# user_interface.net
KiCad netlist of a schematic drawn in Altium Designer
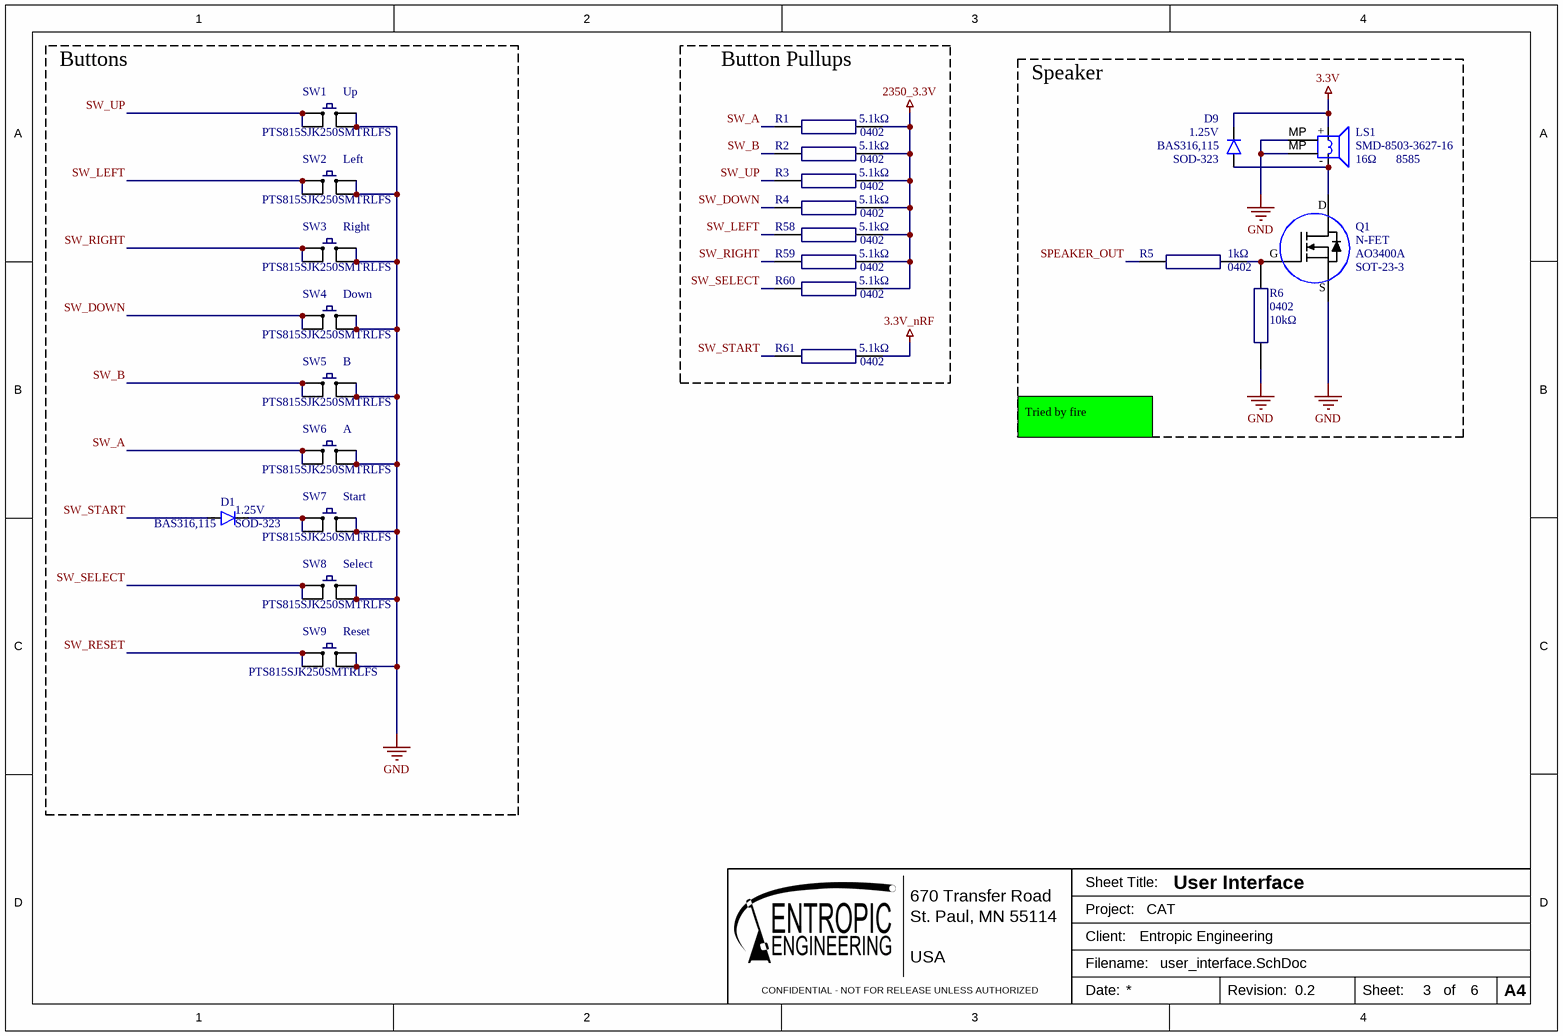
[diagram p0: user_interface.SchDoc]

(export (version "E")
  (design (tool "Eeschema 10.0.6"))
  (components
    (comp (ref "D1")
      (value "BAS316,115")
      (footprint "SOD-323")
      (description "1.25 V, 100 V max, 150 mA, 4 ns diode, SOD-323")
      (fields
        (field (name "MANUFACTURER") "Nexperia")
        (field (name "MANUFACTURER PART NUMBER") "BAS316,115")
        (field (name "FORWARD VOLTAGE") "1.25V")
        (field (name "PACKAGE") "SOD-323")
      )
      (libsource (lib "cat") (part "BAS316,115"))
    )
    (comp (ref "D9")
      (value "BAS316,115")
      (footprint "SOD-323")
      (description "1.25 V, 100 V max, 150 mA, 4 ns diode, SOD-323")
      (fields
        (field (name "MANUFACTURER") "Nexperia")
        (field (name "MANUFACTURER PART NUMBER") "BAS316,115")
        (field (name "FORWARD VOLTAGE") "1.25V")
        (field (name "PACKAGE") "SOD-323")
      )
      (libsource (lib "cat") (part "BAS316,115"))
    )
    (comp (ref "LS1")
      (value "SMD-8503-3627-16")
      (footprint "8585_speaker")
      (description "16 Ω, 8.5 mm x 8.5 mm, SMD speaker")
      (fields
        (field (name "MANUFACTURER") "S&S")
        (field (name "RESISTANCE") "16Ω")
        (field (name "PACKAGE") "8585")
        (field (name "MANUFACTURER PART NUMBER") "SMD-8503-3627-16")
      )
      (libsource (lib "cat") (part "SMD-8503-3627-16"))
    )
    (comp (ref "Q1")
      (value "N-FET")
      (footprint "SOT95P280X115-3N")
      (description "N-FET, 30V, 5.7A, SOT-23-3")
      (fields
        (field (name "MANUFACTURER") "Alpha & Omega Semiconductor")
        (field (name "CASE/PACKAGE") "SOT-23-3")
        (field (name "MANUFACTURER PART NUMBER") "AO3400A")
        (field (name "HOUSE_PART_NUMBER") "AO3400A")
      )
      (libsource (lib "cat") (part "AO3400A"))
    )
    (comp (ref "R1")
      (value "5.1kΩ")
      (footprint "0402_resistor")
      (description "5.1 kΩ, 0402 Chip resistor")
      (fields
        (field (name "MANUFACTURER") "Yageo")
        (field (name "MANUFACTURER PART NUMBER") "RC0402FR-075K1L")
        (field (name "CASE/PACKAGE") "0402")
      )
      (libsource (lib "cat") (part "RC0402FR-075K1L"))
    )
    (comp (ref "R2")
      (value "5.1kΩ")
      (footprint "0402_resistor")
      (description "5.1 kΩ, 0402 Chip resistor")
      (fields
        (field (name "MANUFACTURER") "Yageo")
        (field (name "MANUFACTURER PART NUMBER") "RC0402FR-075K1L")
        (field (name "CASE/PACKAGE") "0402")
      )
      (libsource (lib "cat") (part "RC0402FR-075K1L"))
    )
    (comp (ref "R3")
      (value "5.1kΩ")
      (footprint "0402_resistor")
      (description "5.1 kΩ, 0402 Chip resistor")
      (fields
        (field (name "MANUFACTURER") "Yageo")
        (field (name "MANUFACTURER PART NUMBER") "RC0402FR-075K1L")
        (field (name "CASE/PACKAGE") "0402")
      )
      (libsource (lib "cat") (part "RC0402FR-075K1L"))
    )
    (comp (ref "R4")
      (value "5.1kΩ")
      (footprint "0402_resistor")
      (description "5.1 kΩ, 0402 Chip resistor")
      (fields
        (field (name "MANUFACTURER") "Yageo")
        (field (name "MANUFACTURER PART NUMBER") "RC0402FR-075K1L")
        (field (name "CASE/PACKAGE") "0402")
      )
      (libsource (lib "cat") (part "RC0402FR-075K1L"))
    )
    (comp (ref "R5")
      (value "1kΩ")
      (footprint "0402_resistor")
      (description "1 kΩ, 0402 Chip resistor")
      (fields
        (field (name "MANUFACTURER") "Yageo")
        (field (name "MANUFACTURER PART NUMBER") "RC0402JR-071KL")
        (field (name "CASE/PACKAGE") "0402")
      )
      (libsource (lib "cat") (part "RC0402JR-071KL"))
    )
    (comp (ref "R6")
      (value "10kΩ")
      (footprint "0402_resistor")
      (description "10 kΩ, 0402 Chip resistor")
      (fields
        (field (name "MANUFACTURER") "Yageo")
        (field (name "MANUFACTURER PART NUMBER") "RC0402FR-0710KL")
        (field (name "CASE CODE (IMPERIAL)") "0402")
      )
      (libsource (lib "cat") (part "RC0402FR-0710KL"))
    )
    (comp (ref "R58")
      (value "5.1kΩ")
      (footprint "0402_resistor")
      (description "5.1 kΩ, 0402 Chip resistor")
      (fields
        (field (name "MANUFACTURER") "Yageo")
        (field (name "MANUFACTURER PART NUMBER") "RC0402FR-075K1L")
        (field (name "CASE/PACKAGE") "0402")
      )
      (libsource (lib "cat") (part "RC0402FR-075K1L"))
    )
    (comp (ref "R59")
      (value "5.1kΩ")
      (footprint "0402_resistor")
      (description "5.1 kΩ, 0402 Chip resistor")
      (fields
        (field (name "MANUFACTURER") "Yageo")
        (field (name "MANUFACTURER PART NUMBER") "RC0402FR-075K1L")
        (field (name "CASE/PACKAGE") "0402")
      )
      (libsource (lib "cat") (part "RC0402FR-075K1L"))
    )
    (comp (ref "R60")
      (value "5.1kΩ")
      (footprint "0402_resistor")
      (description "5.1 kΩ, 0402 Chip resistor")
      (fields
        (field (name "MANUFACTURER") "Yageo")
        (field (name "MANUFACTURER PART NUMBER") "RC0402FR-075K1L")
        (field (name "CASE/PACKAGE") "0402")
      )
      (libsource (lib "cat") (part "RC0402FR-075K1L"))
    )
    (comp (ref "R61")
      (value "5.1kΩ")
      (footprint "0402_resistor")
      (description "5.1 kΩ, 0402 Chip resistor")
      (fields
        (field (name "MANUFACTURER") "Yageo")
        (field (name "MANUFACTURER PART NUMBER") "RC0402FR-075K1L")
        (field (name "CASE/PACKAGE") "0402")
      )
      (libsource (lib "cat") (part "RC0402FR-075K1L"))
    )
    (comp (ref "SW1")
      (value "Up")
      (footprint "PTS815")
      (description "Surface Mount Tactile Switch, Momentary SPST-NO 50mA 12VDC, 250gf, 4.2x3.2mm")
      (fields
        (field (name "MANUFACTURER PART NUMBER") "PTS815SJK250SMTRLFS")
        (field (name "MANUFACTURER") "ITT C&K")
      )
      (libsource (lib "cat") (part "PTS815SJK250SMTRLFS"))
    )
    (comp (ref "SW2")
      (value "Left")
      (footprint "PTS815")
      (description "Surface Mount Tactile Switch, Momentary SPST-NO 50mA 12VDC, 250gf, 4.2x3.2mm")
      (fields
        (field (name "MANUFACTURER PART NUMBER") "PTS815SJK250SMTRLFS")
        (field (name "MANUFACTURER") "ITT C&K")
      )
      (libsource (lib "cat") (part "PTS815SJK250SMTRLFS"))
    )
    (comp (ref "SW3")
      (value "Right")
      (footprint "PTS815")
      (description "Surface Mount Tactile Switch, Momentary SPST-NO 50mA 12VDC, 250gf, 4.2x3.2mm")
      (fields
        (field (name "MANUFACTURER PART NUMBER") "PTS815SJK250SMTRLFS")
        (field (name "MANUFACTURER") "ITT C&K")
      )
      (libsource (lib "cat") (part "PTS815SJK250SMTRLFS"))
    )
    (comp (ref "SW4")
      (value "Down")
      (footprint "PTS815")
      (description "Surface Mount Tactile Switch, Momentary SPST-NO 50mA 12VDC, 250gf, 4.2x3.2mm")
      (fields
        (field (name "MANUFACTURER PART NUMBER") "PTS815SJK250SMTRLFS")
        (field (name "MANUFACTURER") "ITT C&K")
      )
      (libsource (lib "cat") (part "PTS815SJK250SMTRLFS"))
    )
    (comp (ref "SW5")
      (value "B")
      (footprint "PTS815")
      (description "Surface Mount Tactile Switch, Momentary SPST-NO 50mA 12VDC, 250gf, 4.2x3.2mm")
      (fields
        (field (name "MANUFACTURER PART NUMBER") "PTS815SJK250SMTRLFS")
        (field (name "MANUFACTURER") "ITT C&K")
      )
      (libsource (lib "cat") (part "PTS815SJK250SMTRLFS"))
    )
    (comp (ref "SW6")
      (value "A")
      (footprint "PTS815")
      (description "Surface Mount Tactile Switch, Momentary SPST-NO 50mA 12VDC, 250gf, 4.2x3.2mm")
      (fields
        (field (name "MANUFACTURER PART NUMBER") "PTS815SJK250SMTRLFS")
        (field (name "MANUFACTURER") "ITT C&K")
      )
      (libsource (lib "cat") (part "PTS815SJK250SMTRLFS"))
    )
    (comp (ref "SW7")
      (value "Start")
      (footprint "PTS815")
      (description "Surface Mount Tactile Switch, Momentary SPST-NO 50mA 12VDC, 250gf, 4.2x3.2mm")
      (fields
        (field (name "MANUFACTURER PART NUMBER") "PTS815SJK250SMTRLFS")
        (field (name "MANUFACTURER") "ITT C&K")
      )
      (libsource (lib "cat") (part "PTS815SJK250SMTRLFS"))
    )
    (comp (ref "SW8")
      (value "Select")
      (footprint "PTS815")
      (description "Surface Mount Tactile Switch, Momentary SPST-NO 50mA 12VDC, 250gf, 4.2x3.2mm")
      (fields
        (field (name "MANUFACTURER PART NUMBER") "PTS815SJK250SMTRLFS")
        (field (name "MANUFACTURER") "ITT C&K")
      )
      (libsource (lib "cat") (part "PTS815SJK250SMTRLFS"))
    )
    (comp (ref "SW9")
      (value "Reset")
      (footprint "PTS815")
      (description "Surface Mount Tactile Switch, Momentary SPST-NO 50mA 12VDC, 250gf, 4.2x3.2mm")
      (fields
        (field (name "MANUFACTURER PART NUMBER") "PTS815SJK250SMTRLFS")
        (field (name "MANUFACTURER") "ITT C&K")
      )
      (libsource (lib "cat") (part "PTS815SJK250SMTRLFS"))
    )
  )
  (nets
    (net (code "1") (name "/SPEAKER_OUT") (class "Default")
      (node (ref "R5") (pin "1") (pinfunction "1_1") (pintype "passive"))
    )
    (net (code "2") (name "/SW_A") (class "Default")
      (node (ref "R1") (pin "2") (pinfunction "2_2") (pintype "passive"))
      (node (ref "SW6") (pin "1") (pinfunction "1_1") (pintype "passive"))
      (node (ref "SW6") (pin "2") (pinfunction "2_2") (pintype "passive"))
    )
    (net (code "3") (name "/SW_B") (class "Default")
      (node (ref "R2") (pin "2") (pinfunction "2_2") (pintype "passive"))
      (node (ref "SW5") (pin "1") (pinfunction "1_1") (pintype "passive"))
      (node (ref "SW5") (pin "2") (pinfunction "2_2") (pintype "passive"))
    )
    (net (code "4") (name "/SW_DOWN") (class "Default")
      (node (ref "R4") (pin "2") (pinfunction "2_2") (pintype "passive"))
      (node (ref "SW4") (pin "1") (pinfunction "1_1") (pintype "passive"))
      (node (ref "SW4") (pin "2") (pinfunction "2_2") (pintype "passive"))
    )
    (net (code "5") (name "/SW_LEFT") (class "Default")
      (node (ref "R58") (pin "2") (pinfunction "2_2") (pintype "passive"))
      (node (ref "SW2") (pin "1") (pinfunction "1_1") (pintype "passive"))
      (node (ref "SW2") (pin "2") (pinfunction "2_2") (pintype "passive"))
    )
    (net (code "6") (name "/SW_RESET") (class "Default")
      (node (ref "SW9") (pin "3") (pinfunction "3_3") (pintype "passive"))
      (node (ref "SW9") (pin "4") (pinfunction "4_4") (pintype "passive"))
    )
    (net (code "7") (name "/SW_RIGHT") (class "Default")
      (node (ref "R59") (pin "2") (pinfunction "2_2") (pintype "passive"))
      (node (ref "SW3") (pin "1") (pinfunction "1_1") (pintype "passive"))
      (node (ref "SW3") (pin "2") (pinfunction "2_2") (pintype "passive"))
    )
    (net (code "8") (name "/SW_SELECT") (class "Default")
      (node (ref "R60") (pin "2") (pinfunction "2_2") (pintype "passive"))
      (node (ref "SW8") (pin "1") (pinfunction "1_1") (pintype "passive"))
      (node (ref "SW8") (pin "2") (pinfunction "2_2") (pintype "passive"))
    )
    (net (code "9") (name "/SW_START") (class "Default")
      (node (ref "D1") (pin "A") (pinfunction "A_A") (pintype "passive"))
      (node (ref "R61") (pin "2") (pinfunction "2_2") (pintype "passive"))
    )
    (net (code "10") (name "/SW_UP") (class "Default")
      (node (ref "R3") (pin "2") (pinfunction "2_2") (pintype "passive"))
      (node (ref "SW1") (pin "1") (pinfunction "1_1") (pintype "passive"))
      (node (ref "SW1") (pin "2") (pinfunction "2_2") (pintype "passive"))
    )
    (net (code "11") (name "3.3V") (class "Default")
      (node (ref "D9") (pin "K") (pinfunction "K_K") (pintype "passive"))
      (node (ref "LS1") (pin "+") (pinfunction "+_+") (pintype "passive"))
    )
    (net (code "12") (name "3.3V_nRF") (class "Default")
      (node (ref "R61") (pin "1") (pinfunction "1_1") (pintype "passive"))
    )
    (net (code "13") (name "2350_3.3V") (class "Default")
      (node (ref "R1") (pin "1") (pinfunction "1_1") (pintype "passive"))
      (node (ref "R2") (pin "1") (pinfunction "1_1") (pintype "passive"))
      (node (ref "R3") (pin "1") (pinfunction "1_1") (pintype "passive"))
      (node (ref "R4") (pin "1") (pinfunction "1_1") (pintype "passive"))
      (node (ref "R58") (pin "1") (pinfunction "1_1") (pintype "passive"))
      (node (ref "R59") (pin "1") (pinfunction "1_1") (pintype "passive"))
      (node (ref "R60") (pin "1") (pinfunction "1_1") (pintype "passive"))
    )
    (net (code "14") (name "GND") (class "Default")
      (node (ref "LS1") (pin "MP") (pinfunction "MP_MP") (pintype "power_in"))
      (node (ref "Q1") (pin "2") (pinfunction "S_2") (pintype "power_in"))
      (node (ref "R6") (pin "2") (pinfunction "2_2") (pintype "passive"))
      (node (ref "SW1") (pin "3") (pinfunction "3_3") (pintype "passive"))
      (node (ref "SW1") (pin "4") (pinfunction "4_4") (pintype "passive"))
      (node (ref "SW2") (pin "3") (pinfunction "3_3") (pintype "passive"))
      (node (ref "SW2") (pin "4") (pinfunction "4_4") (pintype "passive"))
      (node (ref "SW3") (pin "3") (pinfunction "3_3") (pintype "passive"))
      (node (ref "SW3") (pin "4") (pinfunction "4_4") (pintype "passive"))
      (node (ref "SW4") (pin "3") (pinfunction "3_3") (pintype "passive"))
      (node (ref "SW4") (pin "4") (pinfunction "4_4") (pintype "passive"))
      (node (ref "SW5") (pin "3") (pinfunction "3_3") (pintype "passive"))
      (node (ref "SW5") (pin "4") (pinfunction "4_4") (pintype "passive"))
      (node (ref "SW6") (pin "3") (pinfunction "3_3") (pintype "passive"))
      (node (ref "SW6") (pin "4") (pinfunction "4_4") (pintype "passive"))
      (node (ref "SW7") (pin "3") (pinfunction "3_3") (pintype "passive"))
      (node (ref "SW7") (pin "4") (pinfunction "4_4") (pintype "passive"))
      (node (ref "SW8") (pin "3") (pinfunction "3_3") (pintype "passive"))
      (node (ref "SW8") (pin "4") (pinfunction "4_4") (pintype "passive"))
      (node (ref "SW9") (pin "1") (pinfunction "1_1") (pintype "passive"))
      (node (ref "SW9") (pin "2") (pinfunction "2_2") (pintype "passive"))
    )
    (net (code "15") (name "Net-(D1-PadK)") (class "Default")
      (node (ref "D1") (pin "K") (pinfunction "K_K") (pintype "passive"))
      (node (ref "SW7") (pin "1") (pinfunction "1_1") (pintype "passive"))
      (node (ref "SW7") (pin "2") (pinfunction "2_2") (pintype "passive"))
    )
    (net (code "16") (name "Net-(Q1-D)") (class "Default")
      (node (ref "D9") (pin "A") (pinfunction "A_A") (pintype "passive"))
      (node (ref "LS1") (pin "-") (pinfunction "-_-") (pintype "passive"))
      (node (ref "Q1") (pin "3") (pinfunction "D_3") (pintype "power_in"))
    )
    (net (code "17") (name "Net-(Q1-G)") (class "Default")
      (node (ref "Q1") (pin "1") (pinfunction "G_1") (pintype "power_in"))
      (node (ref "R5") (pin "2") (pinfunction "2_2") (pintype "passive"))
      (node (ref "R6") (pin "1") (pinfunction "1_1") (pintype "passive"))
    )
  )
)
